# SiLPA_HE_CPCIS_Con_P1_P6.net
KiCad netlist of a schematic drawn in Altium Designer
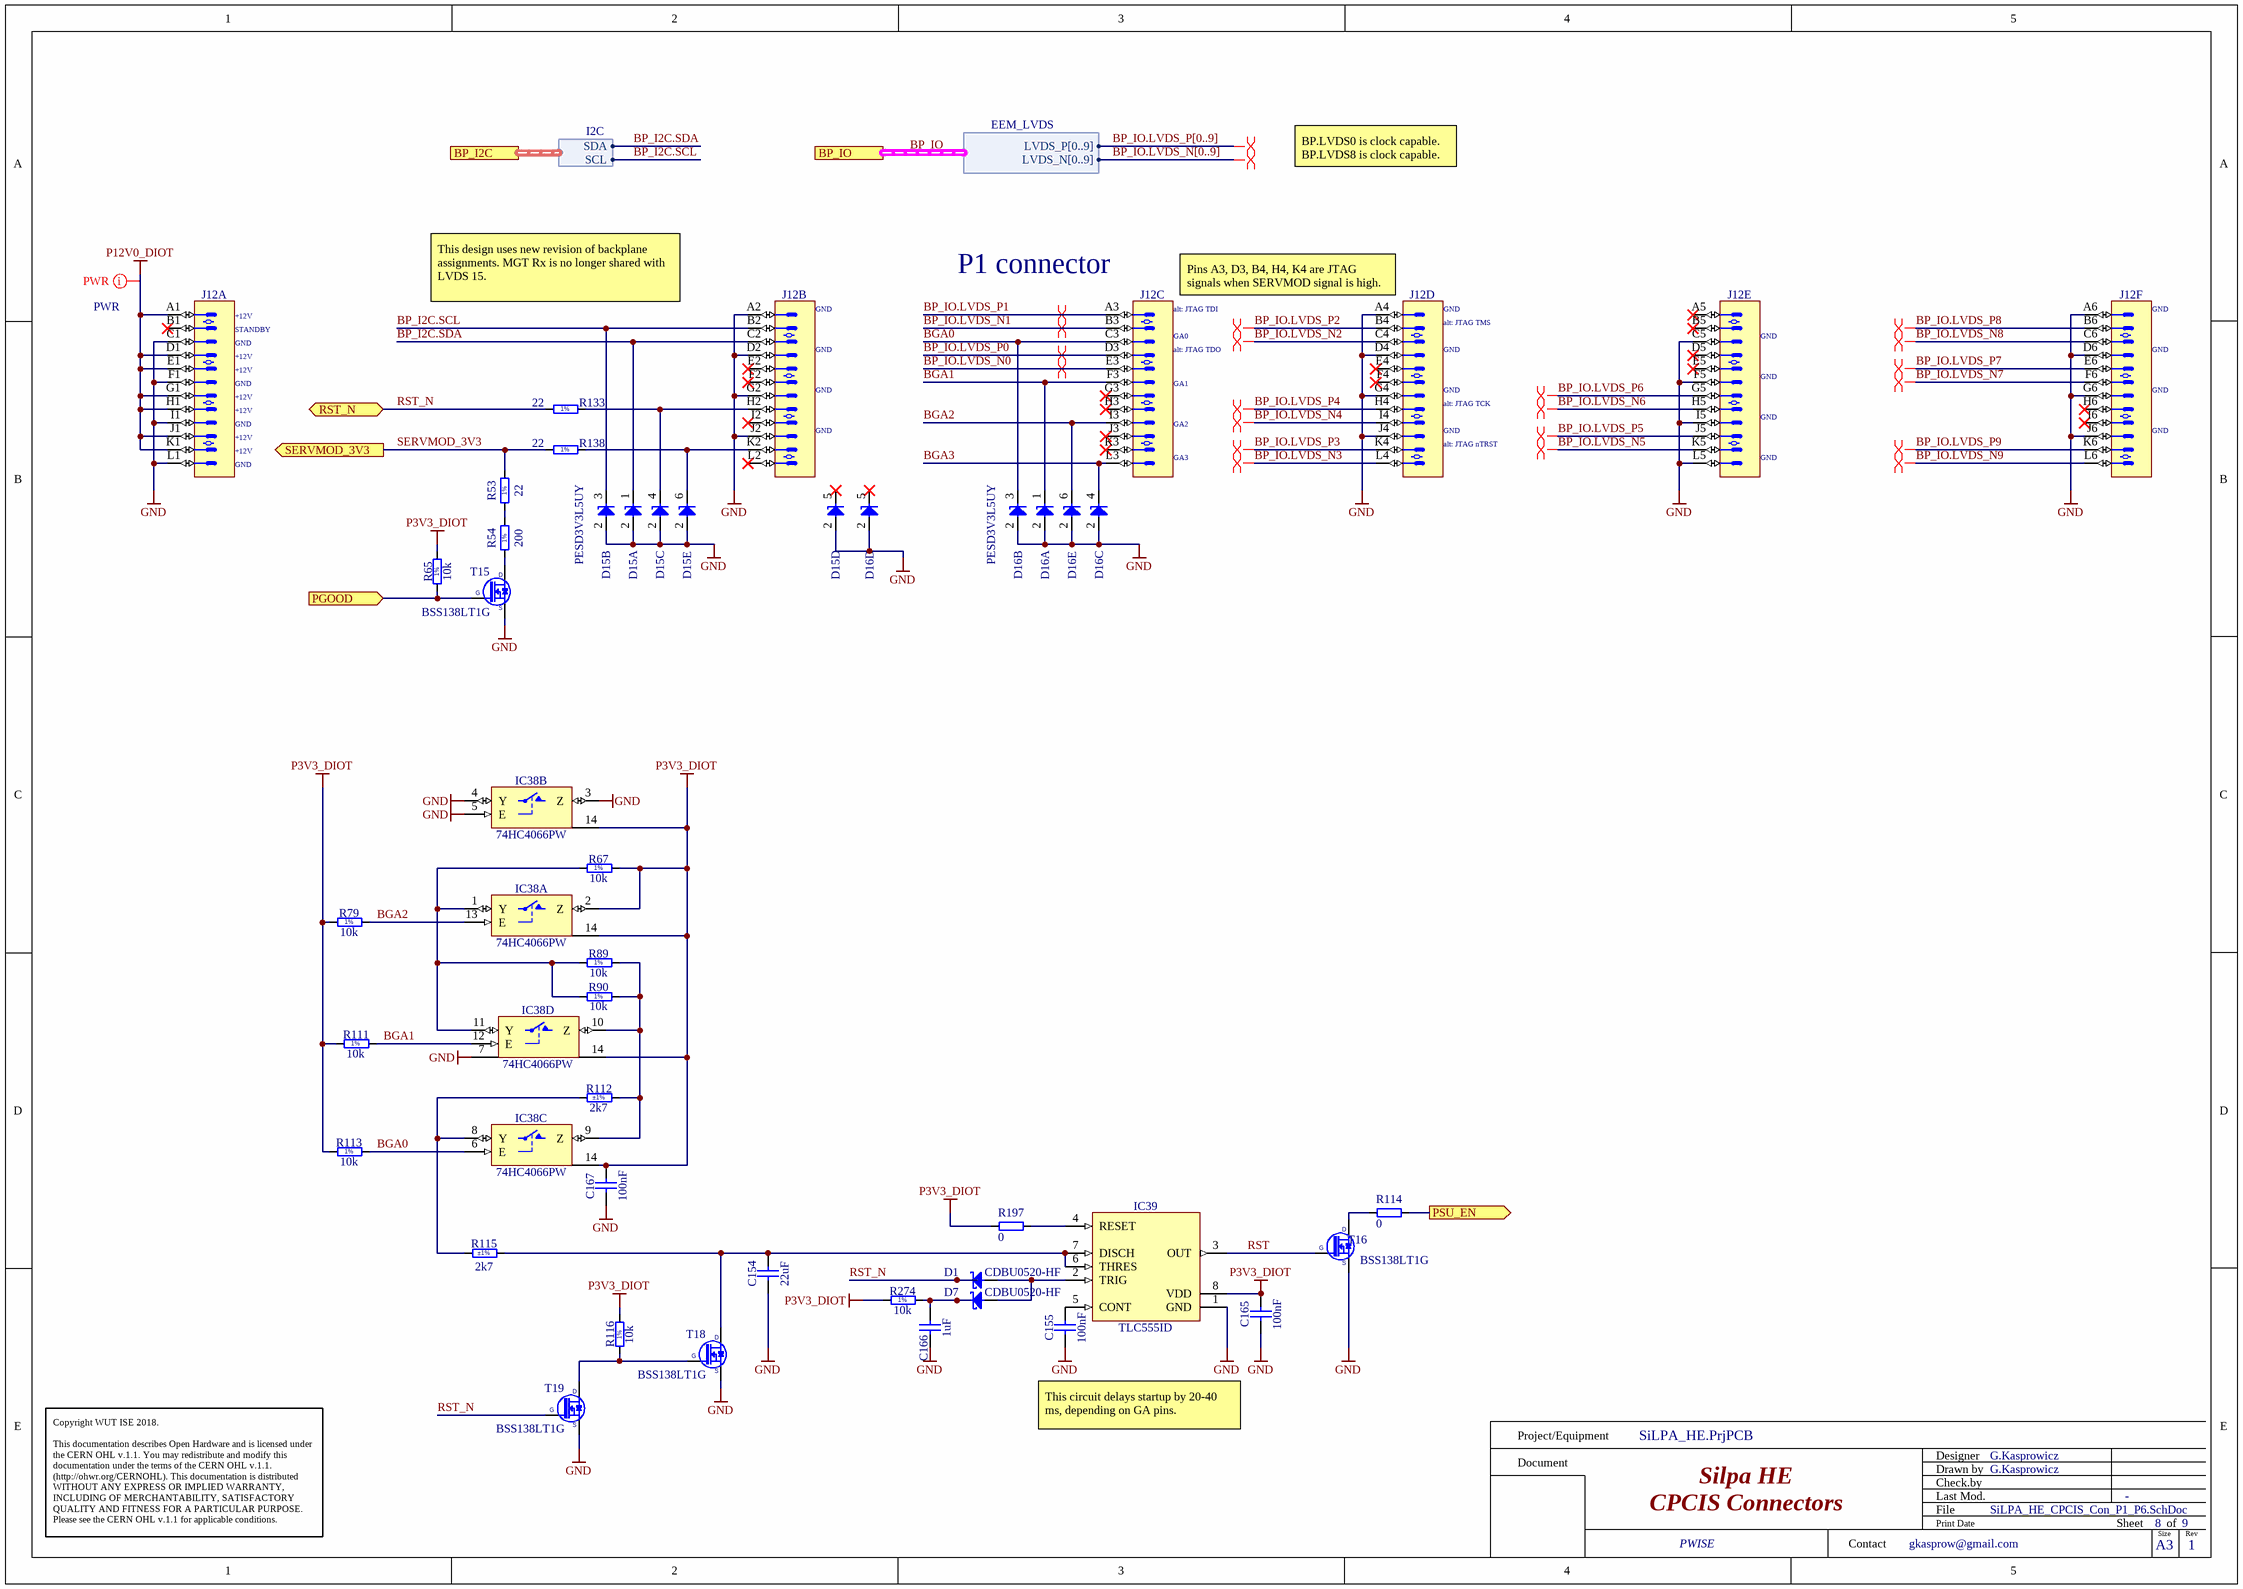
[diagram p0: SiLPA_HE_CPCIS_Con_P1_P6.SchDoc]

(export (version "E")
  (design (tool "Eeschema 10.0.6"))
  (components
    (comp (ref "C154")
      (value "22uF")
      (footprint "CAPC1608X90N")
      (description "Non-polarised capacitor")
      (fields
        (field (name "MANUFACTURER") "GENERIC")
        (field (name "PART NUMBER") "CC0603_22UF_6.3V_20%_X5R")
        (field (name "AUTHOR") "CERN DEM JLC")
      )
      (libsource (lib "EEM_FMC_Carrier") (part "CC0603_22UF_6.3V_20%_X5R"))
    )
    (comp (ref "C155")
      (value "100nF")
      (footprint "CAPC1005X55N")
      (description "Non-polarised capacitor")
      (fields
        (field (name "PART NUMBER") "CC0402_100NF_16V_10%_X5R")
        (field (name "VOLTAGE") "16V")
        (field (name "AUTHOR") "CERN DEM JLC")
      )
      (libsource (lib "EEM_FMC_Carrier") (part "CC0402_100NF_16V_10%_X5R"))
    )
    (comp (ref "C165")
      (value "100nF")
      (footprint "CAPC1005X55N")
      (description "Non-polarised capacitor")
      (fields
        (field (name "PART NUMBER") "CC0402_100NF_16V_10%_X5R")
        (field (name "VOLTAGE") "16V")
        (field (name "AUTHOR") "CERN DEM JLC")
      )
      (libsource (lib "EEM_FMC_Carrier") (part "CC0402_100NF_16V_10%_X5R"))
    )
    (comp (ref "C166")
      (value "1uF")
      (footprint "CAPC1005X55N")
      (description "Non-polarised capacitor")
      (fields
        (field (name "PART NUMBER") "CC0402_1UF_16V_10%_X5R")
        (field (name "VOLTAGE") "16V")
        (field (name "AUTHOR") "CERN DEM JLC")
      )
      (libsource (lib "EEM_FMC_Carrier") (part "CC0402_1UF_16V_10%_X5R"))
    )
    (comp (ref "C167")
      (value "100nF")
      (footprint "CAPC1005X55N")
      (description "Non-polarised capacitor")
      (fields
        (field (name "PART NUMBER") "CC0402_100NF_16V_10%_X5R")
        (field (name "VOLTAGE") "16V")
        (field (name "AUTHOR") "CERN DEM JLC")
      )
      (libsource (lib "EEM_FMC_Carrier") (part "CC0402_100NF_16V_10%_X5R"))
    )
    (comp (ref "D1")
      (value "CDBU0520-HF")
      (footprint "CDBU")
      (description "Schottky Diode")
      (fields
        (field (name "VOLTAGE") "20V")
        (field (name "POWER") "500mA")
        (field (name "AUTHOR") "CERN DEM HF")
      )
      (libsource (lib "SiLPA") (part "CDBU0520-HF"))
    )
    (comp (ref "D7")
      (value "CDBU0520-HF")
      (footprint "CDBU")
      (description "Schottky Diode")
      (fields
        (field (name "VOLTAGE") "20V")
        (field (name "POWER") "500mA")
        (field (name "AUTHOR") "CERN DEM HF")
      )
      (libsource (lib "SiLPA") (part "CDBU0520-HF"))
    )
    (comp (ref "D15")
      (value "PESD3V3L5UY")
      (footprint "SOT65P210X110-6N")
      (description "Fivefold ESD Protection Diode Arrays")
      (fields
        (field (name "VOLTAGE") "3.3V")
        (field (name "POWER") "200W")
        (field (name "AUTHOR") "CERN DEM WB")
      )
      (libsource (lib "EEM_FMC_Carrier") (part "PESD3V3L5UY"))
    )
    (comp (ref "D16")
      (value "PESD3V3L5UY")
      (footprint "SOT65P210X110-6N")
      (description "Fivefold ESD Protection Diode Arrays")
      (fields
        (field (name "VOLTAGE") "3.3V")
        (field (name "POWER") "200W")
        (field (name "AUTHOR") "CERN DEM WB")
      )
      (libsource (lib "EEM_FMC_Carrier") (part "PESD3V3L5UY"))
    )
    (comp (ref "IC38")
      (value "74HC4066PW")
      (footprint "SOP65P640X110-14N")
      (fields (field (name "MANUFACTURER") "NXP SEMICONDUCTORS") (field (name "AUTHOR") "CERN DEM JLC"))
      (libsource (lib "EEM_FMC_Carrier") (part "74HC4066PW"))
    )
    (comp (ref "IC39")
      (value "TLC555ID")
      (footprint "SOIC127P600X175-8N")
      (description "LinCMOS Timer")
      (fields (field (name "MANUFACTURER") "TEXAS INSTRUMENTS") (field (name "AUTHOR") "CERN DEM JMW"))
      (libsource (lib "EEM_FMC_Carrier") (part "TLC555ID"))
    )
    (comp (ref "J12")
      (value "~")
      (footprint "AMPHENOL_10052825-101LF")
      (description "72 Contacts Header, 6 Columns, 4 Pairs per Column")
      (fields
        (field (name "PART NUMBER") "AMPHENOL_10052825-101LF")
        (field (name "MANUFACTURER") "AMPHENOL")
        (field (name "AUTHOR") "CERN DEM MR")
      )
      (libsource (lib "SiLPA_own") (part "AMPHENOL_10052825-101LF"))
    )
    (comp (ref "R53")
      (value "22")
      (footprint "RESC1005X40N")
      (description "Resistor - 1%")
      (fields
        (field (name "PART NUMBER") "R0402_22R_1%_0.0625W_100PPM")
        (field (name "POWER") "0.0625W")
        (field (name "AUTHOR") "CERN DEM JLC")
      )
      (libsource (lib "EEM_FMC_Carrier") (part "R0402_22R_1%_0.0625W_100PPM"))
    )
    (comp (ref "R54")
      (value "200")
      (footprint "RESC1005X40N")
      (description "Resistor - 1%")
      (fields
        (field (name "PART NUMBER") "R0402_22R_1%_0.0625W_100PPM")
        (field (name "POWER") "0.0625W")
        (field (name "AUTHOR") "CERN DEM JLC")
      )
      (libsource (lib "EEM_FMC_Carrier") (part "R0402_22R_1%_0.0625W_100PPM"))
    )
    (comp (ref "R65")
      (value "10k")
      (footprint "RESC1005X40N")
      (description "Resistor - 1%")
      (fields
        (field (name "PART NUMBER") "R0402_10K_1%_0.0625W_100PPM")
        (field (name "POWER") "0.0625W")
        (field (name "AUTHOR") "CERN DEM JLC")
      )
      (libsource (lib "EEM_FMC_Carrier") (part "R0402_10K_1%_0.0625W_100PPM"))
    )
    (comp (ref "R67")
      (value "10k")
      (footprint "RESC1005X40N")
      (description "Resistor - 1%")
      (fields
        (field (name "PART NUMBER") "R0402_10K_1%_0.0625W_100PPM")
        (field (name "POWER") "0.0625W")
        (field (name "AUTHOR") "CERN DEM JLC")
      )
      (libsource (lib "EEM_FMC_Carrier") (part "R0402_10K_1%_0.0625W_100PPM"))
    )
    (comp (ref "R79")
      (value "10k")
      (footprint "RESC1005X40N")
      (description "Resistor - 1%")
      (fields
        (field (name "PART NUMBER") "R0402_10K_1%_0.0625W_100PPM")
        (field (name "POWER") "0.0625W")
        (field (name "AUTHOR") "CERN DEM JLC")
      )
      (libsource (lib "EEM_FMC_Carrier") (part "R0402_10K_1%_0.0625W_100PPM"))
    )
    (comp (ref "R89")
      (value "10k")
      (footprint "RESC1005X40N")
      (description "Resistor - 1%")
      (fields
        (field (name "PART NUMBER") "R0402_10K_1%_0.0625W_100PPM")
        (field (name "POWER") "0.0625W")
        (field (name "AUTHOR") "CERN DEM JLC")
      )
      (libsource (lib "EEM_FMC_Carrier") (part "R0402_10K_1%_0.0625W_100PPM"))
    )
    (comp (ref "R90")
      (value "10k")
      (footprint "RESC1005X40N")
      (description "Resistor - 1%")
      (fields
        (field (name "PART NUMBER") "R0402_10K_1%_0.0625W_100PPM")
        (field (name "POWER") "0.0625W")
        (field (name "AUTHOR") "CERN DEM JLC")
      )
      (libsource (lib "EEM_FMC_Carrier") (part "R0402_10K_1%_0.0625W_100PPM"))
    )
    (comp (ref "R111")
      (value "10k")
      (footprint "RESC1005X40N")
      (description "Resistor - 1%")
      (fields
        (field (name "PART NUMBER") "R0402_10K_1%_0.0625W_100PPM")
        (field (name "POWER") "0.0625W")
        (field (name "AUTHOR") "CERN DEM JLC")
      )
      (libsource (lib "EEM_FMC_Carrier") (part "R0402_10K_1%_0.0625W_100PPM"))
    )
    (comp (ref "R112")
      (value "2k7")
      (footprint "RESC1608X55N")
      (description "Resistor - 1%")
      (fields
        (field (name "PART NUMBER") "R0603_2K7_1%_0.1W_100PPM")
        (field (name "POWER") "0.1W")
        (field (name "TOLERANCE") "±1%")
        (field (name "AUTHOR") "CERN DEM JLC")
      )
      (libsource (lib "EEM_FMC_Carrier") (part "R0603_2K7_1%_0.1W_100PPM"))
    )
    (comp (ref "R113")
      (value "10k")
      (footprint "RESC1005X40N")
      (description "Resistor - 1%")
      (fields
        (field (name "PART NUMBER") "R0402_10K_1%_0.0625W_100PPM")
        (field (name "POWER") "0.0625W")
        (field (name "AUTHOR") "CERN DEM JLC")
      )
      (libsource (lib "EEM_FMC_Carrier") (part "R0402_10K_1%_0.0625W_100PPM"))
    )
    (comp (ref "R114")
      (value "0")
      (footprint "RESC1005X40N")
      (description "Resistor")
      (fields
        (field (name "PART NUMBER") "R0402_0R_JUMPER")
        (field (name "MANUFACTURER") "GENERIC")
        (field (name "AUTHOR") "CERN DEM JLC")
      )
      (libsource (lib "EEM_FMC_Carrier") (part "R0402_0R_JUMPER"))
    )
    (comp (ref "R115")
      (value "2k7")
      (footprint "RESC1608X55N")
      (description "Resistor - 1%")
      (fields
        (field (name "PART NUMBER") "R0603_2K7_1%_0.1W_100PPM")
        (field (name "POWER") "0.1W")
        (field (name "TOLERANCE") "±1%")
        (field (name "AUTHOR") "CERN DEM JLC")
      )
      (libsource (lib "EEM_FMC_Carrier") (part "R0603_2K7_1%_0.1W_100PPM"))
    )
    (comp (ref "R116")
      (value "10k")
      (footprint "RESC1005X40N")
      (description "Resistor - 1%")
      (fields
        (field (name "PART NUMBER") "R0402_10K_1%_0.0625W_100PPM")
        (field (name "POWER") "0.0625W")
        (field (name "AUTHOR") "CERN DEM JLC")
      )
      (libsource (lib "EEM_FMC_Carrier") (part "R0402_10K_1%_0.0625W_100PPM"))
    )
    (comp (ref "R133")
      (value "22")
      (footprint "RESC1005X40N")
      (description "Resistor - 1%")
      (fields
        (field (name "PART NUMBER") "R0402_22R_1%_0.0625W_100PPM")
        (field (name "POWER") "0.0625W")
        (field (name "AUTHOR") "CERN DEM JLC")
      )
      (libsource (lib "EEM_FMC_Carrier") (part "R0402_22R_1%_0.0625W_100PPM"))
    )
    (comp (ref "R138")
      (value "22")
      (footprint "RESC1005X40N")
      (description "Resistor - 1%")
      (fields
        (field (name "PART NUMBER") "R0402_22R_1%_0.0625W_100PPM")
        (field (name "POWER") "0.0625W")
        (field (name "AUTHOR") "CERN DEM JLC")
      )
      (libsource (lib "EEM_FMC_Carrier") (part "R0402_22R_1%_0.0625W_100PPM"))
    )
    (comp (ref "R197")
      (value "0")
      (footprint "RESC1005X40N")
      (description "Resistor")
      (fields
        (field (name "PART NUMBER") "R0402_0R_JUMPER")
        (field (name "MANUFACTURER") "GENERIC")
        (field (name "AUTHOR") "CERN DEM JLC")
      )
      (libsource (lib "EEM_FMC_Carrier") (part "R0402_0R_JUMPER"))
    )
    (comp (ref "R274")
      (value "10k")
      (footprint "RESC1005X40N")
      (description "Resistor - 1%")
      (fields
        (field (name "PART NUMBER") "R0402_10K_1%_0.0625W_100PPM")
        (field (name "POWER") "0.0625W")
        (field (name "AUTHOR") "CERN DEM JLC")
      )
      (libsource (lib "EEM_FMC_Carrier") (part "R0402_10K_1%_0.0625W_100PPM"))
    )
    (comp (ref "T15")
      (value "BSS138LT1G")
      (footprint "SOT95P240X110-3N")
      (description "N-CHANNEL MOSFET WITH DIODE")
      (fields (field (name "MANUFACTURER") "ON SEMICONDUCTOR") (field (name "AUTHOR") "CERN DEM JLC"))
      (libsource (lib "ICs And Semiconductors") (part "N-MOSFET-D 1G 2S 3D"))
    )
    (comp (ref "T16")
      (value "BSS138LT1G")
      (footprint "SOT95P240X110-3N")
      (description "N-CHANNEL MOSFET WITH DIODE")
      (fields (field (name "MANUFACTURER") "ON SEMICONDUCTOR") (field (name "AUTHOR") "CERN DEM JLC"))
      (libsource (lib "ICs And Semiconductors") (part "N-MOSFET-D 1G 2S 3D"))
    )
    (comp (ref "T18")
      (value "BSS138LT1G")
      (footprint "SOT95P240X110-3N")
      (description "N-CHANNEL MOSFET WITH DIODE")
      (fields (field (name "MANUFACTURER") "ON SEMICONDUCTOR") (field (name "AUTHOR") "CERN DEM JLC"))
      (libsource (lib "ICs And Semiconductors") (part "N-MOSFET-D 1G 2S 3D"))
    )
    (comp (ref "T19")
      (value "BSS138LT1G")
      (footprint "SOT95P240X110-3N")
      (description "N-CHANNEL MOSFET WITH DIODE")
      (fields (field (name "MANUFACTURER") "ON SEMICONDUCTOR") (field (name "AUTHOR") "CERN DEM JLC"))
      (libsource (lib "ICs And Semiconductors") (part "N-MOSFET-D 1G 2S 3D"))
    )
  )
  (nets
    (net (code "3") (name "/BGA0") (class "Default")
      (node (ref "D16") (pin "3") (pinfunction "C_3") (pintype "passive"))
      (node (ref "IC38") (pin "6") (pinfunction "E_6") (pintype "input"))
      (node (ref "J12") (pin "C3") (pinfunction "C3_C3") (pintype "bidirectional"))
      (node (ref "R113") (pin "2") (pinfunction "2_2") (pintype "passive"))
    )
    (net (code "4") (name "/BGA1") (class "Default")
      (node (ref "D16") (pin "1") (pinfunction "C_1") (pintype "passive"))
      (node (ref "IC38") (pin "12") (pinfunction "E_12") (pintype "input"))
      (node (ref "J12") (pin "F3") (pinfunction "F3_F3") (pintype "bidirectional"))
      (node (ref "R111") (pin "2") (pinfunction "2_2") (pintype "passive"))
    )
    (net (code "5") (name "/BGA2") (class "Default")
      (node (ref "D16") (pin "6") (pinfunction "C_6") (pintype "passive"))
      (node (ref "IC38") (pin "13") (pinfunction "E_13") (pintype "input"))
      (node (ref "J12") (pin "I3") (pinfunction "I3_I3") (pintype "bidirectional"))
      (node (ref "R79") (pin "2") (pinfunction "2_2") (pintype "passive"))
    )
    (net (code "6") (name "/BGA3") (class "Default")
      (node (ref "D16") (pin "4") (pinfunction "C_4") (pintype "passive"))
      (node (ref "J12") (pin "L3") (pinfunction "L3_L3") (pintype "bidirectional"))
    )
    (net (code "7") (name "/BP_I2C.SCL") (class "Default")
      (node (ref "D15") (pin "3") (pinfunction "C_3") (pintype "passive"))
      (node (ref "J12") (pin "B2") (pinfunction "B2_B2") (pintype "bidirectional"))
    )
    (net (code "8") (name "/BP_I2C.SDA") (class "Default")
      (node (ref "D15") (pin "1") (pinfunction "C_1") (pintype "passive"))
      (node (ref "J12") (pin "C2") (pinfunction "C2_C2") (pintype "bidirectional"))
    )
    (net (code "9") (name "/BP_IO.LVDS_N0") (class "Default")
      (node (ref "J12") (pin "E3") (pinfunction "E3_E3") (pintype "bidirectional"))
    )
    (net (code "10") (name "/BP_IO.LVDS_N1") (class "Default")
      (node (ref "J12") (pin "B3") (pinfunction "B3_B3") (pintype "bidirectional"))
    )
    (net (code "11") (name "/BP_IO.LVDS_N2") (class "Default")
      (node (ref "J12") (pin "C4") (pinfunction "C4_C4") (pintype "bidirectional"))
    )
    (net (code "12") (name "/BP_IO.LVDS_N3") (class "Default")
      (node (ref "J12") (pin "L4") (pinfunction "L4_L4") (pintype "bidirectional"))
    )
    (net (code "13") (name "/BP_IO.LVDS_N4") (class "Default")
      (node (ref "J12") (pin "I4") (pinfunction "I4_I4") (pintype "bidirectional"))
    )
    (net (code "14") (name "/BP_IO.LVDS_N5") (class "Default")
      (node (ref "J12") (pin "K5") (pinfunction "K5_K5") (pintype "bidirectional"))
    )
    (net (code "15") (name "/BP_IO.LVDS_N6") (class "Default")
      (node (ref "J12") (pin "H5") (pinfunction "H5_H5") (pintype "bidirectional"))
    )
    (net (code "16") (name "/BP_IO.LVDS_N7") (class "Default")
      (node (ref "J12") (pin "F6") (pinfunction "F6_F6") (pintype "bidirectional"))
    )
    (net (code "17") (name "/BP_IO.LVDS_N8") (class "Default")
      (node (ref "J12") (pin "C6") (pinfunction "C6_C6") (pintype "bidirectional"))
    )
    (net (code "18") (name "/BP_IO.LVDS_N9") (class "Default")
      (node (ref "J12") (pin "L6") (pinfunction "L6_L6") (pintype "bidirectional"))
    )
    (net (code "20") (name "/BP_IO.LVDS_P0") (class "Default")
      (node (ref "J12") (pin "D3") (pinfunction "D3_D3") (pintype "bidirectional"))
    )
    (net (code "21") (name "/BP_IO.LVDS_P1") (class "Default")
      (node (ref "J12") (pin "A3") (pinfunction "A3_A3") (pintype "bidirectional"))
    )
    (net (code "22") (name "/BP_IO.LVDS_P2") (class "Default")
      (node (ref "J12") (pin "B4") (pinfunction "B4_B4") (pintype "bidirectional"))
    )
    (net (code "23") (name "/BP_IO.LVDS_P3") (class "Default")
      (node (ref "J12") (pin "K4") (pinfunction "K4_K4") (pintype "bidirectional"))
    )
    (net (code "24") (name "/BP_IO.LVDS_P4") (class "Default")
      (node (ref "J12") (pin "H4") (pinfunction "H4_H4") (pintype "bidirectional"))
    )
    (net (code "25") (name "/BP_IO.LVDS_P5") (class "Default")
      (node (ref "J12") (pin "J5") (pinfunction "J5_J5") (pintype "bidirectional"))
    )
    (net (code "26") (name "/BP_IO.LVDS_P6") (class "Default")
      (node (ref "J12") (pin "G5") (pinfunction "G5_G5") (pintype "bidirectional"))
    )
    (net (code "27") (name "/BP_IO.LVDS_P7") (class "Default")
      (node (ref "J12") (pin "E6") (pinfunction "E6_E6") (pintype "bidirectional"))
    )
    (net (code "28") (name "/BP_IO.LVDS_P8") (class "Default")
      (node (ref "J12") (pin "B6") (pinfunction "B6_B6") (pintype "bidirectional"))
    )
    (net (code "29") (name "/BP_IO.LVDS_P9") (class "Default")
      (node (ref "J12") (pin "K6") (pinfunction "K6_K6") (pintype "bidirectional"))
    )
    (net (code "32") (name "/PGOOD") (class "Default")
      (node (ref "R65") (pin "1") (pinfunction "1_1") (pintype "passive"))
      (node (ref "T15") (pin "1") (pinfunction "G_1") (pintype "passive"))
    )
    (net (code "33") (name "/PSU_EN") (class "Default")
      (node (ref "R114") (pin "1") (pinfunction "1_1") (pintype "passive"))
    )
    (net (code "34") (name "/RST") (class "Default")
      (node (ref "IC39") (pin "3") (pinfunction "OUT_3") (pintype "output"))
      (node (ref "T16") (pin "1") (pinfunction "G_1") (pintype "passive"))
    )
    (net (code "35") (name "/RST_N") (class "Default")
      (node (ref "D1") (pin "1") (pinfunction "C_1") (pintype "passive"))
      (node (ref "R133") (pin "1") (pinfunction "1_1") (pintype "passive"))
      (node (ref "T19") (pin "1") (pinfunction "G_1") (pintype "passive"))
    )
    (net (code "36") (name "/SERVMOD_3V3") (class "Default")
      (node (ref "R138") (pin "1") (pinfunction "1_1") (pintype "passive"))
      (node (ref "R53") (pin "2") (pinfunction "2_2") (pintype "passive"))
    )
    (net (code "38") (name "GND") (class "Default")
      (node (ref "C154") (pin "1") (pinfunction "1_1") (pintype "passive"))
      (node (ref "C155") (pin "1") (pinfunction "1_1") (pintype "passive"))
      (node (ref "C165") (pin "1") (pinfunction "1_1") (pintype "passive"))
      (node (ref "C166") (pin "1") (pinfunction "1_1") (pintype "passive"))
      (node (ref "C167") (pin "1") (pinfunction "1_1") (pintype "passive"))
      (node (ref "D15") (pin "2") (pinfunction "A_2") (pintype "passive"))
      (node (ref "D16") (pin "2") (pinfunction "A_2") (pintype "passive"))
      (node (ref "IC38") (pin "3") (pinfunction "Z_3") (pintype "bidirectional"))
      (node (ref "IC38") (pin "4") (pinfunction "Y_4") (pintype "bidirectional"))
      (node (ref "IC38") (pin "5") (pinfunction "E_5") (pintype "input"))
      (node (ref "IC38") (pin "7") (pinfunction "GND_7") (pintype "power_in"))
      (node (ref "IC39") (pin "1") (pinfunction "GND_1") (pintype "power_in"))
      (node (ref "J12") (pin "A2") (pinfunction "A2_A2") (pintype "bidirectional"))
      (node (ref "J12") (pin "A4") (pinfunction "A4_A4") (pintype "bidirectional"))
      (node (ref "J12") (pin "A6") (pinfunction "A6_A6") (pintype "bidirectional"))
      (node (ref "J12") (pin "C1") (pinfunction "C1_C1") (pintype "bidirectional"))
      (node (ref "J12") (pin "C5") (pinfunction "C5_C5") (pintype "bidirectional"))
      (node (ref "J12") (pin "D2") (pinfunction "D2_D2") (pintype "bidirectional"))
      (node (ref "J12") (pin "D4") (pinfunction "D4_D4") (pintype "bidirectional"))
      (node (ref "J12") (pin "D6") (pinfunction "D6_D6") (pintype "bidirectional"))
      (node (ref "J12") (pin "F1") (pinfunction "F1_F1") (pintype "bidirectional"))
      (node (ref "J12") (pin "F5") (pinfunction "F5_F5") (pintype "bidirectional"))
      (node (ref "J12") (pin "G2") (pinfunction "G2_G2") (pintype "bidirectional"))
      (node (ref "J12") (pin "G4") (pinfunction "G4_G4") (pintype "bidirectional"))
      (node (ref "J12") (pin "G6") (pinfunction "G6_G6") (pintype "bidirectional"))
      (node (ref "J12") (pin "I1") (pinfunction "I1_I1") (pintype "bidirectional"))
      (node (ref "J12") (pin "I5") (pinfunction "I5_I5") (pintype "bidirectional"))
      (node (ref "J12") (pin "J2") (pinfunction "J2_J2") (pintype "bidirectional"))
      (node (ref "J12") (pin "J4") (pinfunction "J4_J4") (pintype "bidirectional"))
      (node (ref "J12") (pin "J6") (pinfunction "J6_J6") (pintype "bidirectional"))
      (node (ref "J12") (pin "L1") (pinfunction "L1_L1") (pintype "bidirectional"))
      (node (ref "J12") (pin "L5") (pinfunction "L5_L5") (pintype "bidirectional"))
      (node (ref "T15") (pin "2") (pinfunction "S_2") (pintype "passive"))
      (node (ref "T16") (pin "2") (pinfunction "S_2") (pintype "passive"))
      (node (ref "T18") (pin "2") (pinfunction "S_2") (pintype "passive"))
      (node (ref "T19") (pin "2") (pinfunction "S_2") (pintype "passive"))
    )
    (net (code "39") (name "Net-(D1-A)") (class "Default")
      (node (ref "D1") (pin "2") (pinfunction "A_2") (pintype "passive"))
      (node (ref "D7") (pin "2") (pinfunction "A_2") (pintype "passive"))
      (node (ref "IC39") (pin "2") (pinfunction "TRIG_2") (pintype "input"))
    )
    (net (code "40") (name "Net-(D7-C)") (class "Default")
      (node (ref "C166") (pin "2") (pinfunction "2_2") (pintype "passive"))
      (node (ref "D7") (pin "1") (pinfunction "C_1") (pintype "passive"))
      (node (ref "R274") (pin "2") (pinfunction "2_2") (pintype "passive"))
    )
    (net (code "41") (name "Net-(D15C-C)") (class "Default")
      (node (ref "D15") (pin "4") (pinfunction "C_4") (pintype "passive"))
      (node (ref "J12") (pin "H2") (pinfunction "H2_H2") (pintype "bidirectional"))
      (node (ref "R133") (pin "2") (pinfunction "2_2") (pintype "passive"))
    )
    (net (code "42") (name "Net-(D15E-C)") (class "Default")
      (node (ref "D15") (pin "6") (pinfunction "C_6") (pintype "passive"))
      (node (ref "J12") (pin "K2") (pinfunction "K2_K2") (pintype "bidirectional"))
      (node (ref "R138") (pin "2") (pinfunction "2_2") (pintype "passive"))
    )
    (net (code "43") (name "Net-(IC38A-Y)") (class "Default")
      (node (ref "IC38") (pin "1") (pinfunction "Y_1") (pintype "bidirectional"))
      (node (ref "IC38") (pin "11") (pinfunction "Y_11") (pintype "bidirectional"))
      (node (ref "R67") (pin "1") (pinfunction "1_1") (pintype "passive"))
      (node (ref "R89") (pin "1") (pinfunction "1_1") (pintype "passive"))
      (node (ref "R90") (pin "1") (pinfunction "1_1") (pintype "passive"))
    )
    (net (code "44") (name "Net-(IC38C-Y)") (class "Default")
      (node (ref "IC38") (pin "8") (pinfunction "Y_8") (pintype "bidirectional"))
      (node (ref "R112") (pin "1") (pinfunction "1_1") (pintype "passive"))
      (node (ref "R115") (pin "1") (pinfunction "1_1") (pintype "passive"))
    )
    (net (code "45") (name "Net-(IC38C-Z)") (class "Default")
      (node (ref "IC38") (pin "10") (pinfunction "Z_10") (pintype "bidirectional"))
      (node (ref "IC38") (pin "9") (pinfunction "Z_9") (pintype "bidirectional"))
      (node (ref "R112") (pin "2") (pinfunction "2_2") (pintype "passive"))
      (node (ref "R89") (pin "2") (pinfunction "2_2") (pintype "passive"))
      (node (ref "R90") (pin "2") (pinfunction "2_2") (pintype "passive"))
    )
    (net (code "46") (name "Net-(IC39-CONT)") (class "Default")
      (node (ref "C155") (pin "2") (pinfunction "2_2") (pintype "passive"))
      (node (ref "IC39") (pin "5") (pinfunction "CONT_5") (pintype "input"))
    )
    (net (code "47") (name "Net-(IC39-DISCH)") (class "Default")
      (node (ref "C154") (pin "2") (pinfunction "2_2") (pintype "passive"))
      (node (ref "IC39") (pin "6") (pinfunction "THRES_6") (pintype "input"))
      (node (ref "IC39") (pin "7") (pinfunction "DISCH_7") (pintype "input"))
      (node (ref "R115") (pin "2") (pinfunction "2_2") (pintype "passive"))
      (node (ref "T18") (pin "3") (pinfunction "D_3") (pintype "passive"))
    )
    (net (code "48") (name "Net-(IC39-RESET)") (class "Default")
      (node (ref "IC39") (pin "4") (pinfunction "RESET_4") (pintype "input"))
      (node (ref "R197") (pin "1") (pinfunction "1_1") (pintype "passive"))
    )
    (net (code "49") (name "Net-(R53-Pad1)") (class "Default")
      (node (ref "R53") (pin "1") (pinfunction "1_1") (pintype "passive"))
      (node (ref "R54") (pin "2") (pinfunction "2_2") (pintype "passive"))
    )
    (net (code "50") (name "Net-(T15-D)") (class "Default")
      (node (ref "R54") (pin "1") (pinfunction "1_1") (pintype "passive"))
      (node (ref "T15") (pin "3") (pinfunction "D_3") (pintype "passive"))
    )
    (net (code "51") (name "Net-(T16-D)") (class "Default")
      (node (ref "R114") (pin "2") (pinfunction "2_2") (pintype "passive"))
      (node (ref "T16") (pin "3") (pinfunction "D_3") (pintype "passive"))
    )
    (net (code "52") (name "Net-(T18-G)") (class "Default")
      (node (ref "R116") (pin "1") (pinfunction "1_1") (pintype "passive"))
      (node (ref "T18") (pin "1") (pinfunction "G_1") (pintype "passive"))
      (node (ref "T19") (pin "3") (pinfunction "D_3") (pintype "passive"))
    )
    (net (code "53") (name "P3V3_DIOT") (class "Default")
      (node (ref "C165") (pin "2") (pinfunction "2_2") (pintype "passive"))
      (node (ref "C167") (pin "2") (pinfunction "2_2") (pintype "passive"))
      (node (ref "IC38") (pin "14") (pinfunction "VCC_14") (pintype "power_in"))
      (node (ref "IC38") (pin "2") (pinfunction "Z_2") (pintype "bidirectional"))
      (node (ref "IC39") (pin "8") (pinfunction "VDD_8") (pintype "power_in"))
      (node (ref "R111") (pin "1") (pinfunction "1_1") (pintype "passive"))
      (node (ref "R113") (pin "1") (pinfunction "1_1") (pintype "passive"))
      (node (ref "R116") (pin "2") (pinfunction "2_2") (pintype "passive"))
      (node (ref "R197") (pin "2") (pinfunction "2_2") (pintype "passive"))
      (node (ref "R274") (pin "1") (pinfunction "1_1") (pintype "passive"))
      (node (ref "R65") (pin "2") (pinfunction "2_2") (pintype "passive"))
      (node (ref "R67") (pin "2") (pinfunction "2_2") (pintype "passive"))
      (node (ref "R79") (pin "1") (pinfunction "1_1") (pintype "passive"))
    )
    (net (code "54") (name "P12V0_DIOT") (class "Default")
      (node (ref "J12") (pin "A1") (pinfunction "A1_A1") (pintype "bidirectional"))
      (node (ref "J12") (pin "D1") (pinfunction "D1_D1") (pintype "bidirectional"))
      (node (ref "J12") (pin "E1") (pinfunction "E1_E1") (pintype "bidirectional"))
      (node (ref "J12") (pin "G1") (pinfunction "G1_G1") (pintype "bidirectional"))
      (node (ref "J12") (pin "H1") (pinfunction "H1_H1") (pintype "bidirectional"))
      (node (ref "J12") (pin "J1") (pinfunction "J1_J1") (pintype "bidirectional"))
      (node (ref "J12") (pin "K1") (pinfunction "K1_K1") (pintype "bidirectional"))
    )
    (net (code "55") (name "unconnected-(D15D-C-Pad5)") (class "Default")
      (node (ref "D15") (pin "5") (pinfunction "C_5") (pintype "passive+no_connect"))
    )
    (net (code "56") (name "unconnected-(D16D-C-Pad5)") (class "Default")
      (node (ref "D16") (pin "5") (pinfunction "C_5") (pintype "passive+no_connect"))
    )
    (net (code "57") (name "unconnected-(J12-PadA5)") (class "Default")
      (node (ref "J12") (pin "A5") (pinfunction "A5_A5") (pintype "bidirectional+no_connect"))
    )
    (net (code "58") (name "unconnected-(J12-PadB1)") (class "Default")
      (node (ref "J12") (pin "B1") (pinfunction "B1_B1") (pintype "bidirectional+no_connect"))
    )
    (net (code "59") (name "unconnected-(J12-PadB5)") (class "Default")
      (node (ref "J12") (pin "B5") (pinfunction "B5_B5") (pintype "bidirectional+no_connect"))
    )
    (net (code "60") (name "unconnected-(J12-PadD5)") (class "Default")
      (node (ref "J12") (pin "D5") (pinfunction "D5_D5") (pintype "bidirectional+no_connect"))
    )
    (net (code "61") (name "unconnected-(J12-PadE2)") (class "Default")
      (node (ref "J12") (pin "E2") (pinfunction "E2_E2") (pintype "bidirectional+no_connect"))
    )
    (net (code "62") (name "unconnected-(J12-PadE4)") (class "Default")
      (node (ref "J12") (pin "E4") (pinfunction "E4_E4") (pintype "bidirectional+no_connect"))
    )
    (net (code "63") (name "unconnected-(J12-PadE5)") (class "Default")
      (node (ref "J12") (pin "E5") (pinfunction "E5_E5") (pintype "bidirectional+no_connect"))
    )
    (net (code "64") (name "unconnected-(J12-PadF2)") (class "Default")
      (node (ref "J12") (pin "F2") (pinfunction "F2_F2") (pintype "bidirectional+no_connect"))
    )
    (net (code "65") (name "unconnected-(J12-PadF4)") (class "Default")
      (node (ref "J12") (pin "F4") (pinfunction "F4_F4") (pintype "bidirectional+no_connect"))
    )
    (net (code "66") (name "unconnected-(J12-PadG3)") (class "Default")
      (node (ref "J12") (pin "G3") (pinfunction "G3_G3") (pintype "bidirectional+no_connect"))
    )
    (net (code "67") (name "unconnected-(J12-PadH3)") (class "Default")
      (node (ref "J12") (pin "H3") (pinfunction "H3_H3") (pintype "bidirectional+no_connect"))
    )
    (net (code "68") (name "unconnected-(J12-PadH6)") (class "Default")
      (node (ref "J12") (pin "H6") (pinfunction "H6_H6") (pintype "bidirectional+no_connect"))
    )
    (net (code "69") (name "unconnected-(J12-PadI2)") (class "Default")
      (node (ref "J12") (pin "I2") (pinfunction "I2_I2") (pintype "bidirectional+no_connect"))
    )
    (net (code "70") (name "unconnected-(J12-PadI6)") (class "Default")
      (node (ref "J12") (pin "I6") (pinfunction "I6_I6") (pintype "bidirectional+no_connect"))
    )
    (net (code "71") (name "unconnected-(J12-PadJ3)") (class "Default")
      (node (ref "J12") (pin "J3") (pinfunction "J3_J3") (pintype "bidirectional+no_connect"))
    )
    (net (code "72") (name "unconnected-(J12-PadK3)") (class "Default")
      (node (ref "J12") (pin "K3") (pinfunction "K3_K3") (pintype "bidirectional+no_connect"))
    )
    (net (code "73") (name "unconnected-(J12-PadL2)") (class "Default")
      (node (ref "J12") (pin "L2") (pinfunction "L2_L2") (pintype "bidirectional+no_connect"))
    )
  )
)
